# RGB-to-VGA.net
KiCad netlist of a schematic drawn in Altium Designer
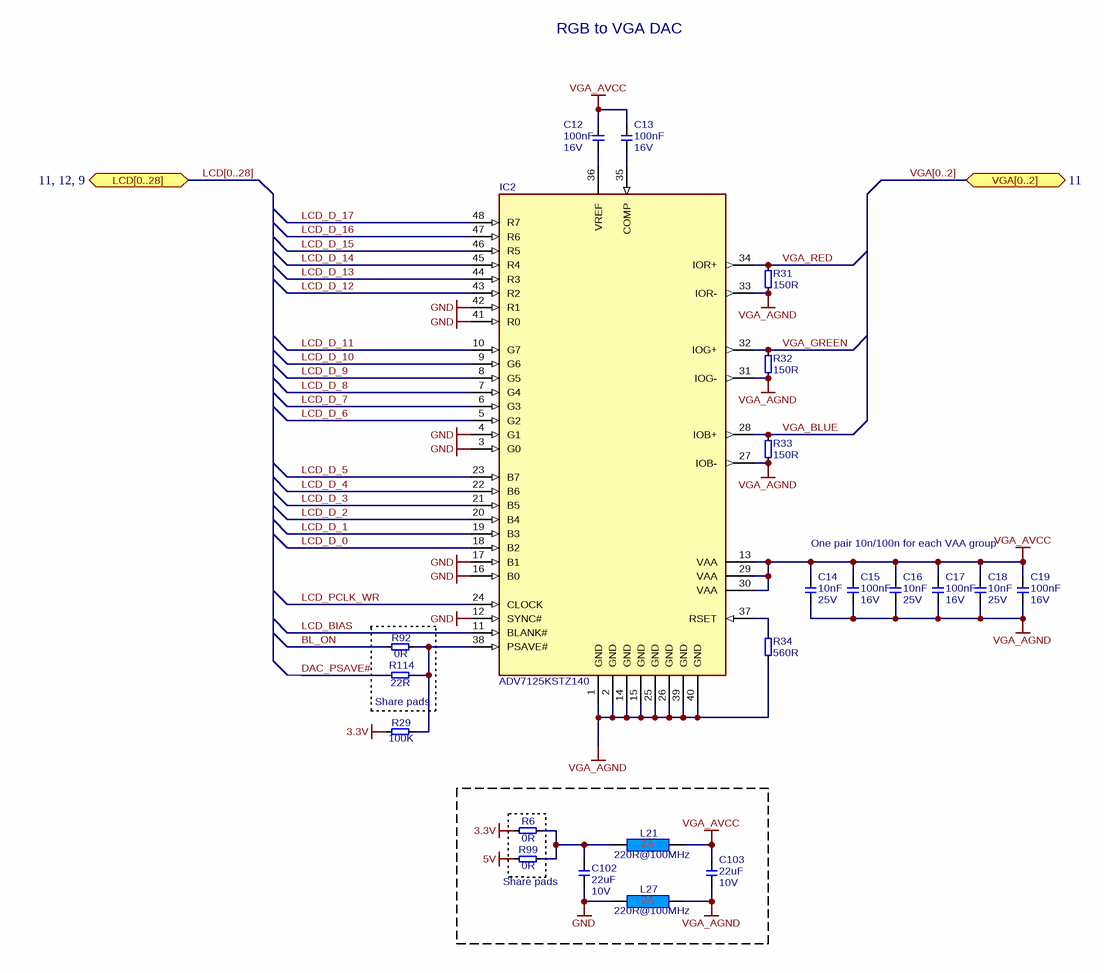
[diagram p0: RGB-to-VGA.SchDoc]

(export (version "E")
  (design (tool "Eeschema 10.0.6"))
  (components
    (comp (ref "C12")
      (value "100nF")
      (footprint "CAPC1005X60N")
      (description "Capacitor Ceramic X7R 100nF 16V 10% 0402")
      (fields (field (name "TOLERANCE") "10%") (field (name "RATING") "16V"))
      (libsource (lib "Iris") (part "C-X7R-100nF-16V-10%-0402"))
    )
    (comp (ref "C13")
      (value "100nF")
      (footprint "CAPC1005X60N")
      (description "Capacitor Ceramic X7R 100nF 16V 10% 0402")
      (fields (field (name "TOLERANCE") "10%") (field (name "RATING") "16V"))
      (libsource (lib "Iris") (part "C-X7R-100nF-16V-10%-0402"))
    )
    (comp (ref "C14")
      (value "10nF")
      (footprint "CAPC1005X60N")
      (description "Capacitor Ceramic X7R 10nF 25V 10% 0402")
      (fields (field (name "TOLERANCE") "10%") (field (name "RATING") "25V"))
      (libsource (lib "Iris") (part "C-X7R-10nF-25V-10%-0402"))
    )
    (comp (ref "C15")
      (value "100nF")
      (footprint "CAPC1005X60N")
      (description "Capacitor Ceramic X7R 100nF 16V 10% 0402")
      (fields (field (name "TOLERANCE") "10%") (field (name "RATING") "16V"))
      (libsource (lib "Iris") (part "C-X7R-100nF-16V-10%-0402"))
    )
    (comp (ref "C16")
      (value "10nF")
      (footprint "CAPC1005X60N")
      (description "Capacitor Ceramic X7R 10nF 25V 10% 0402")
      (fields (field (name "TOLERANCE") "10%") (field (name "RATING") "25V"))
      (libsource (lib "Iris") (part "C-X7R-10nF-25V-10%-0402"))
    )
    (comp (ref "C17")
      (value "100nF")
      (footprint "CAPC1005X60N")
      (description "Capacitor Ceramic X7R 100nF 16V 10% 0402")
      (fields (field (name "TOLERANCE") "10%") (field (name "RATING") "16V"))
      (libsource (lib "Iris") (part "C-X7R-100nF-16V-10%-0402"))
    )
    (comp (ref "C18")
      (value "10nF")
      (footprint "CAPC1005X60N")
      (description "Capacitor Ceramic X7R 10nF 25V 10% 0402")
      (fields (field (name "TOLERANCE") "10%") (field (name "RATING") "25V"))
      (libsource (lib "Iris") (part "C-X7R-10nF-25V-10%-0402"))
    )
    (comp (ref "C19")
      (value "100nF")
      (footprint "CAPC1005X60N")
      (description "Capacitor Ceramic X7R 100nF 16V 10% 0402")
      (fields (field (name "TOLERANCE") "10%") (field (name "RATING") "16V"))
      (libsource (lib "Iris") (part "C-X7R-100nF-16V-10%-0402"))
    )
    (comp (ref "C102")
      (value "22uF")
      (footprint "T_CAPC0805X125N")
      (description "Capacitor Ceramic X5R 22uF 10V 20% 0805")
      (fields (field (name "TOLERANCE") "20%") (field (name "RATING") "10V"))
      (libsource (lib "Iris") (part "C-X5R-22uF-10V-20%-0805"))
    )
    (comp (ref "C103")
      (value "22uF")
      (footprint "T_CAPC0805X125N")
      (description "Capacitor Ceramic X5R 22uF 10V 20% 0805")
      (fields (field (name "TOLERANCE") "20%") (field (name "RATING") "10V"))
      (libsource (lib "Iris") (part "C-X5R-22uF-10V-20%-0805"))
    )
    (comp (ref "IC2")
      (value "ADV7125KSTZ140")
      (footprint "QFP50P900X900X120-48N")
      (description "Video DAC 8bit 140MHz")
      (fields (field (name "MANUFACTURER PART NO.") "ADV7125KSTZ140"))
      (libsource (lib "Iris") (part "IC-AD-ADV7125KSTZ140"))
    )
    (comp (ref "L21")
      (value "220R@100MHz")
      (footprint "INDC1608X95N")
      (description "220R@100MHz 2A EMI FILTER")
      (fields (field (name "TOLERANCE") "25%"))
      (libsource (lib "Iris") (part "L-220R@100MHz-2A-25%-0603"))
    )
    (comp (ref "L27")
      (value "220R@100MHz")
      (footprint "INDC1608X95N")
      (description "220R@100MHz 2A EMI FILTER")
      (fields (field (name "TOLERANCE") "25%"))
      (libsource (lib "Iris") (part "L-220R@100MHz-2A-25%-0603"))
    )
    (comp (ref "R6")
      (value "0R")
      (footprint "T_RESC0603X30N")
      (description "Resistor 0 ohm 63mW 5% 0603")
      (fields (field (name "TOLERANCE") "5%"))
      (libsource (lib "Iris") (part "R-0R-63mW-5%-0603"))
    )
    (comp (ref "R29")
      (value "100K")
      (footprint "T_RESC0603X30N")
      (description "Resistor 100 Kohm 63mW 5% 0603")
      (fields (field (name "TOLERANCE") "5%"))
      (libsource (lib "Iris") (part "R-100KR-63mW-5%-0603"))
    )
    (comp (ref "R31")
      (value "150R")
      (footprint "RESC1005X40N")
      (description "Resistor 150 ohm 63mW 5% 0402")
      (fields (field (name "TOLERANCE") "5%"))
      (libsource (lib "Iris") (part "R-150R-63mW-5%-0402"))
    )
    (comp (ref "R32")
      (value "150R")
      (footprint "RESC1005X40N")
      (description "Resistor 150 ohm 63mW 5% 0402")
      (fields (field (name "TOLERANCE") "5%"))
      (libsource (lib "Iris") (part "R-150R-63mW-5%-0402"))
    )
    (comp (ref "R33")
      (value "150R")
      (footprint "RESC1005X40N")
      (description "Resistor 150 ohm 63mW 5% 0402")
      (fields (field (name "TOLERANCE") "5%"))
      (libsource (lib "Iris") (part "R-150R-63mW-5%-0402"))
    )
    (comp (ref "R34")
      (value "560R")
      (footprint "RESC1005X40N")
      (description "Resistor 560 ohm 63mW 5% 0402")
      (fields (field (name "TOLERANCE") "5%"))
      (libsource (lib "Iris") (part "R-560R-63mW-5%-0402"))
    )
    (comp (ref "R92")
      (value "0R")
      (footprint "T_RESC0603X30N")
      (description "Resistor 0 ohm 63mW 5% 0603")
      (fields (field (name "TOLERANCE") "5%"))
      (libsource (lib "Iris") (part "R-0R-63mW-5%-0603"))
    )
    (comp (ref "R99")
      (value "0R")
      (footprint "T_RESC0603X30N")
      (description "Resistor 0 ohm 63mW 5% 0603")
      (fields (field (name "TOLERANCE") "5%"))
      (libsource (lib "Iris") (part "R-0R-63mW-5%-0603"))
    )
    (comp (ref "R114")
      (value "22R")
      (footprint "T_RESC0603X30N")
      (description "Resistor 22 ohm 63mW 5% 0603")
      (fields (field (name "TOLERANCE") "5%"))
      (libsource (lib "Iris") (part "R-22R-63mW-5%-0603"))
    )
  )
  (nets
    (net (code "33") (name "/BL_ON") (class "Default")
      (node (ref "R92") (pin "1") (pinfunction "1_1") (pintype "passive"))
    )
    (net (code "34") (name "/DAC_PSAVE#") (class "Default")
      (node (ref "R114") (pin "1") (pinfunction "1_1") (pintype "passive"))
    )
    (net (code "36") (name "/LCD_BIAS") (class "Default")
      (node (ref "IC2") (pin "11") (pinfunction "BLANK#_11") (pintype "input"))
    )
    (net (code "37") (name "/LCD_D_0") (class "Default")
      (node (ref "IC2") (pin "18") (pinfunction "B2_18") (pintype "input"))
    )
    (net (code "38") (name "/LCD_D_1") (class "Default")
      (node (ref "IC2") (pin "19") (pinfunction "B3_19") (pintype "input"))
    )
    (net (code "39") (name "/LCD_D_2") (class "Default")
      (node (ref "IC2") (pin "20") (pinfunction "B4_20") (pintype "input"))
    )
    (net (code "40") (name "/LCD_D_3") (class "Default")
      (node (ref "IC2") (pin "21") (pinfunction "B5_21") (pintype "input"))
    )
    (net (code "41") (name "/LCD_D_4") (class "Default")
      (node (ref "IC2") (pin "22") (pinfunction "B6_22") (pintype "input"))
    )
    (net (code "42") (name "/LCD_D_5") (class "Default")
      (node (ref "IC2") (pin "23") (pinfunction "B7_23") (pintype "input"))
    )
    (net (code "43") (name "/LCD_D_6") (class "Default")
      (node (ref "IC2") (pin "5") (pinfunction "G2_5") (pintype "input"))
    )
    (net (code "44") (name "/LCD_D_7") (class "Default")
      (node (ref "IC2") (pin "6") (pinfunction "G3_6") (pintype "input"))
    )
    (net (code "45") (name "/LCD_D_8") (class "Default")
      (node (ref "IC2") (pin "7") (pinfunction "G4_7") (pintype "input"))
    )
    (net (code "46") (name "/LCD_D_9") (class "Default")
      (node (ref "IC2") (pin "8") (pinfunction "G5_8") (pintype "input"))
    )
    (net (code "47") (name "/LCD_D_10") (class "Default")
      (node (ref "IC2") (pin "9") (pinfunction "G6_9") (pintype "input"))
    )
    (net (code "48") (name "/LCD_D_11") (class "Default")
      (node (ref "IC2") (pin "10") (pinfunction "G7_10") (pintype "input"))
    )
    (net (code "49") (name "/LCD_D_12") (class "Default")
      (node (ref "IC2") (pin "43") (pinfunction "R2_43") (pintype "input"))
    )
    (net (code "50") (name "/LCD_D_13") (class "Default")
      (node (ref "IC2") (pin "44") (pinfunction "R3_44") (pintype "input"))
    )
    (net (code "51") (name "/LCD_D_14") (class "Default")
      (node (ref "IC2") (pin "45") (pinfunction "R4_45") (pintype "input"))
    )
    (net (code "52") (name "/LCD_D_15") (class "Default")
      (node (ref "IC2") (pin "46") (pinfunction "R5_46") (pintype "input"))
    )
    (net (code "53") (name "/LCD_D_16") (class "Default")
      (node (ref "IC2") (pin "47") (pinfunction "R6_47") (pintype "input"))
    )
    (net (code "54") (name "/LCD_D_17") (class "Default")
      (node (ref "IC2") (pin "48") (pinfunction "R7_48") (pintype "input"))
    )
    (net (code "55") (name "/LCD_PCLK_WR") (class "Default")
      (node (ref "IC2") (pin "24") (pinfunction "CLOCK_24") (pintype "input"))
    )
    (net (code "57") (name "/VGA_BLUE") (class "Default")
      (node (ref "IC2") (pin "28") (pinfunction "IOB+_28") (pintype "output"))
      (node (ref "R33") (pin "2") (pinfunction "2_2") (pintype "passive"))
    )
    (net (code "58") (name "/VGA_GREEN") (class "Default")
      (node (ref "IC2") (pin "32") (pinfunction "IOG+_32") (pintype "output"))
      (node (ref "R32") (pin "2") (pinfunction "2_2") (pintype "passive"))
    )
    (net (code "59") (name "/VGA_RED") (class "Default")
      (node (ref "IC2") (pin "34") (pinfunction "IOR+_34") (pintype "output"))
      (node (ref "R31") (pin "2") (pinfunction "2_2") (pintype "passive"))
    )
    (net (code "60") (name "3.3V") (class "Default")
      (node (ref "R29") (pin "1") (pinfunction "1_1") (pintype "passive"))
      (node (ref "R6") (pin "1") (pinfunction "1_1") (pintype "passive"))
    )
    (net (code "61") (name "5V") (class "Default")
      (node (ref "R99") (pin "1") (pinfunction "1_1") (pintype "passive"))
    )
    (net (code "62") (name "GND") (class "Default")
      (node (ref "C102") (pin "1") (pinfunction "1_1") (pintype "passive"))
      (node (ref "IC2") (pin "12") (pinfunction "SYNC#_12") (pintype "input"))
      (node (ref "IC2") (pin "16") (pinfunction "B0_16") (pintype "input"))
      (node (ref "IC2") (pin "17") (pinfunction "B1_17") (pintype "input"))
      (node (ref "IC2") (pin "3") (pinfunction "G0_3") (pintype "input"))
      (node (ref "IC2") (pin "4") (pinfunction "G1_4") (pintype "input"))
      (node (ref "IC2") (pin "41") (pinfunction "R0_41") (pintype "input"))
      (node (ref "IC2") (pin "42") (pinfunction "R1_42") (pintype "input"))
      (node (ref "L27") (pin "1") (pinfunction "1_1") (pintype "passive"))
    )
    (net (code "63") (name "Net-(C102-Pad2)") (class "Default")
      (node (ref "C102") (pin "2") (pinfunction "2_2") (pintype "passive"))
      (node (ref "L21") (pin "1") (pinfunction "1_1") (pintype "passive"))
      (node (ref "R6") (pin "2") (pinfunction "2_2") (pintype "passive"))
      (node (ref "R99") (pin "2") (pinfunction "2_2") (pintype "passive"))
    )
    (net (code "64") (name "Net-(IC2-COMP)") (class "Default")
      (node (ref "C13") (pin "1") (pinfunction "1_1") (pintype "passive"))
      (node (ref "IC2") (pin "35") (pinfunction "COMP_35") (pintype "input"))
    )
    (net (code "65") (name "Net-(IC2-PSAVE#)") (class "Default")
      (node (ref "IC2") (pin "38") (pinfunction "PSAVE#_38") (pintype "input"))
      (node (ref "R114") (pin "2") (pinfunction "2_2") (pintype "passive"))
      (node (ref "R29") (pin "2") (pinfunction "2_2") (pintype "passive"))
      (node (ref "R92") (pin "2") (pinfunction "2_2") (pintype "passive"))
    )
    (net (code "66") (name "Net-(IC2-RSET)") (class "Default")
      (node (ref "IC2") (pin "37") (pinfunction "RSET_37") (pintype "input"))
      (node (ref "R34") (pin "2") (pinfunction "2_2") (pintype "passive"))
    )
    (net (code "67") (name "Net-(IC2-VREF)") (class "Default")
      (node (ref "C12") (pin "1") (pinfunction "1_1") (pintype "passive"))
      (node (ref "IC2") (pin "36") (pinfunction "VREF_36") (pintype "power_in"))
    )
    (net (code "68") (name "VGA_AGND") (class "Default")
      (node (ref "C103") (pin "1") (pinfunction "1_1") (pintype "passive"))
      (node (ref "C14") (pin "1") (pinfunction "1_1") (pintype "passive"))
      (node (ref "C15") (pin "1") (pinfunction "1_1") (pintype "passive"))
      (node (ref "C16") (pin "1") (pinfunction "1_1") (pintype "passive"))
      (node (ref "C17") (pin "1") (pinfunction "1_1") (pintype "passive"))
      (node (ref "C18") (pin "1") (pinfunction "1_1") (pintype "passive"))
      (node (ref "C19") (pin "1") (pinfunction "1_1") (pintype "passive"))
      (node (ref "IC2") (pin "1") (pinfunction "GND_1") (pintype "power_in"))
      (node (ref "IC2") (pin "14") (pinfunction "GND_14") (pintype "power_in"))
      (node (ref "IC2") (pin "15") (pinfunction "GND_15") (pintype "power_in"))
      (node (ref "IC2") (pin "2") (pinfunction "GND_2") (pintype "power_in"))
      (node (ref "IC2") (pin "25") (pinfunction "GND_25") (pintype "power_in"))
      (node (ref "IC2") (pin "26") (pinfunction "GND_26") (pintype "power_in"))
      (node (ref "IC2") (pin "27") (pinfunction "IOB-_27") (pintype "output"))
      (node (ref "IC2") (pin "31") (pinfunction "IOG-_31") (pintype "output"))
      (node (ref "IC2") (pin "33") (pinfunction "IOR-_33") (pintype "output"))
      (node (ref "IC2") (pin "39") (pinfunction "GND_39") (pintype "power_in"))
      (node (ref "IC2") (pin "40") (pinfunction "GND_40") (pintype "power_in"))
      (node (ref "L27") (pin "2") (pinfunction "2_2") (pintype "passive"))
      (node (ref "R31") (pin "1") (pinfunction "1_1") (pintype "passive"))
      (node (ref "R32") (pin "1") (pinfunction "1_1") (pintype "passive"))
      (node (ref "R33") (pin "1") (pinfunction "1_1") (pintype "passive"))
      (node (ref "R34") (pin "1") (pinfunction "1_1") (pintype "passive"))
    )
    (net (code "69") (name "VGA_AVCC") (class "Default")
      (node (ref "C103") (pin "2") (pinfunction "2_2") (pintype "passive"))
      (node (ref "C12") (pin "2") (pinfunction "2_2") (pintype "passive"))
      (node (ref "C13") (pin "2") (pinfunction "2_2") (pintype "passive"))
      (node (ref "C14") (pin "2") (pinfunction "2_2") (pintype "passive"))
      (node (ref "C15") (pin "2") (pinfunction "2_2") (pintype "passive"))
      (node (ref "C16") (pin "2") (pinfunction "2_2") (pintype "passive"))
      (node (ref "C17") (pin "2") (pinfunction "2_2") (pintype "passive"))
      (node (ref "C18") (pin "2") (pinfunction "2_2") (pintype "passive"))
      (node (ref "C19") (pin "2") (pinfunction "2_2") (pintype "passive"))
      (node (ref "IC2") (pin "13") (pinfunction "VAA_13") (pintype "power_in"))
      (node (ref "IC2") (pin "29") (pinfunction "VAA_29") (pintype "power_in"))
      (node (ref "IC2") (pin "30") (pinfunction "VAA_30") (pintype "power_in"))
      (node (ref "L21") (pin "2") (pinfunction "2_2") (pintype "passive"))
    )
  )
)
